# pcf1306p-SMD.net
KiCad netlist of a schematic drawn in EAGLE
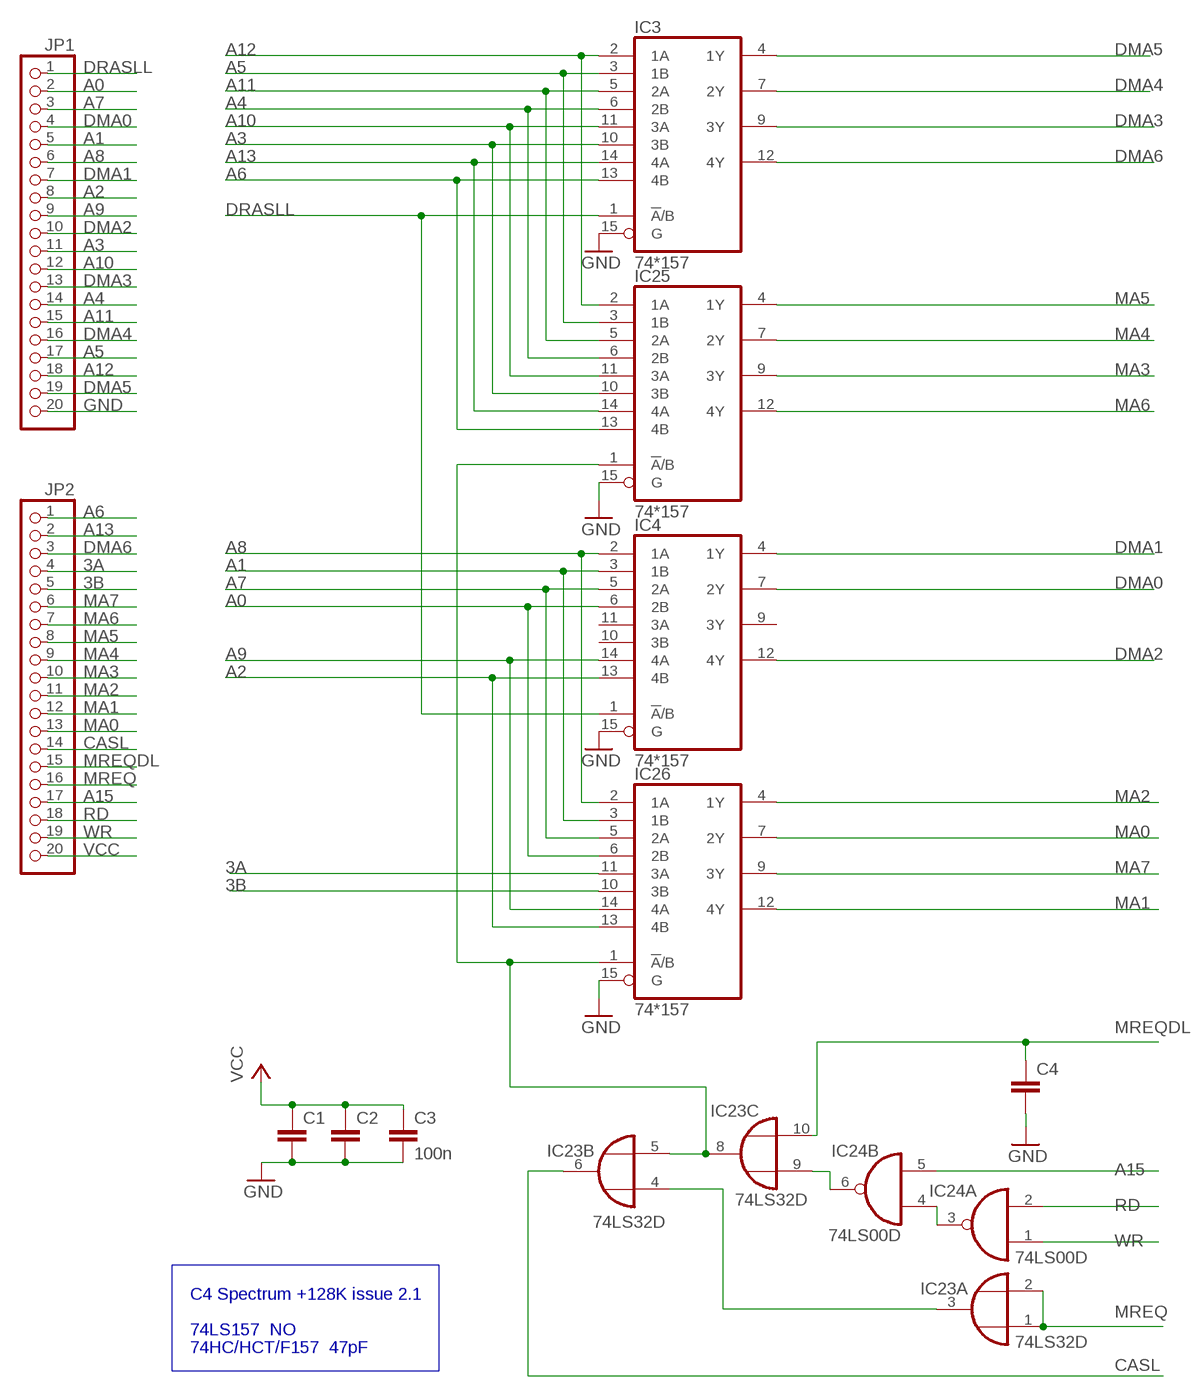
[diagram p0: schematic, sheet 1]

(export (version "E")
  (design (tool "Eeschema 10.0.6"))
  (components
    (comp (ref "C1")
      (value "C-EUC0603")
      (footprint "eagle-import:C0603")
      (libsource (lib "eagle-import") (part "C-EUC0603"))
    )
    (comp (ref "C2")
      (value "C-EUC0603")
      (footprint "eagle-import:C0603")
      (libsource (lib "eagle-import") (part "C-EUC0603"))
    )
    (comp (ref "C3")
      (value "100n")
      (footprint "eagle-import:C0603")
      (libsource (lib "eagle-import") (part "C-EUC0603"))
    )
    (comp (ref "C4")
      (value "C-EUC0805")
      (footprint "eagle-import:C0805")
      (libsource (lib "eagle-import") (part "C-EUC0805"))
    )
    (comp (ref "IC3")
      (value "74*157")
      (footprint "eagle-import:SO16")
      (libsource (lib "eagle-import") (part "74157DLS"))
    )
    (comp (ref "IC4")
      (value "74*157")
      (footprint "eagle-import:SO16")
      (libsource (lib "eagle-import") (part "74157DLS"))
    )
    (comp (ref "IC23")
      (value "74LS32D")
      (footprint "eagle-import:SO14")
      (libsource (lib "eagle-import") (part "7432DLS"))
    )
    (comp (ref "IC24")
      (value "74LS00D")
      (footprint "eagle-import:SO14")
      (libsource (lib "eagle-import") (part "7400DLS"))
    )
    (comp (ref "IC25")
      (value "74*157")
      (footprint "eagle-import:SO16")
      (libsource (lib "eagle-import") (part "74157DLS"))
    )
    (comp (ref "IC26")
      (value "74*157")
      (footprint "eagle-import:SO16")
      (libsource (lib "eagle-import") (part "74157DLS"))
    )
    (comp (ref "JP1")
      (value "PINHD-1X20")
      (footprint "eagle-import:1X20")
      (libsource (lib "eagle-import") (part "PINHD-1X20"))
    )
    (comp (ref "JP2")
      (value "PINHD-1X20")
      (footprint "eagle-import:1X20")
      (libsource (lib "eagle-import") (part "PINHD-1X20"))
    )
  )
  (nets
    (net (code "1") (name "/3A") (class "Default")
      (node (ref "IC26") (pin "11") (pinfunction "3A_11") (pintype "input"))
      (node (ref "JP2") (pin "4") (pinfunction "4_4") (pintype "passive"))
    )
    (net (code "2") (name "/3B") (class "Default")
      (node (ref "IC26") (pin "10") (pinfunction "3B_10") (pintype "input"))
      (node (ref "JP2") (pin "5") (pinfunction "5_5") (pintype "passive"))
    )
    (net (code "3") (name "/A0") (class "Default")
      (node (ref "IC26") (pin "6") (pinfunction "2B_6") (pintype "input"))
      (node (ref "IC4") (pin "6") (pinfunction "2B_6") (pintype "input"))
      (node (ref "JP1") (pin "2") (pinfunction "2_2") (pintype "passive"))
    )
    (net (code "4") (name "/A1") (class "Default")
      (node (ref "IC26") (pin "3") (pinfunction "1B_3") (pintype "input"))
      (node (ref "IC4") (pin "3") (pinfunction "1B_3") (pintype "input"))
      (node (ref "JP1") (pin "5") (pinfunction "5_5") (pintype "passive"))
    )
    (net (code "5") (name "/A2") (class "Default")
      (node (ref "IC26") (pin "13") (pinfunction "4B_13") (pintype "input"))
      (node (ref "IC4") (pin "13") (pinfunction "4B_13") (pintype "input"))
      (node (ref "JP1") (pin "8") (pinfunction "8_8") (pintype "passive"))
    )
    (net (code "6") (name "/A3") (class "Default")
      (node (ref "IC25") (pin "10") (pinfunction "3B_10") (pintype "input"))
      (node (ref "IC3") (pin "10") (pinfunction "3B_10") (pintype "input"))
      (node (ref "JP1") (pin "11") (pinfunction "11_11") (pintype "passive"))
    )
    (net (code "7") (name "/A4") (class "Default")
      (node (ref "IC25") (pin "6") (pinfunction "2B_6") (pintype "input"))
      (node (ref "IC3") (pin "6") (pinfunction "2B_6") (pintype "input"))
      (node (ref "JP1") (pin "14") (pinfunction "14_14") (pintype "passive"))
    )
    (net (code "8") (name "/A5") (class "Default")
      (node (ref "IC25") (pin "3") (pinfunction "1B_3") (pintype "input"))
      (node (ref "IC3") (pin "3") (pinfunction "1B_3") (pintype "input"))
      (node (ref "JP1") (pin "17") (pinfunction "17_17") (pintype "passive"))
    )
    (net (code "9") (name "/A6") (class "Default")
      (node (ref "IC25") (pin "13") (pinfunction "4B_13") (pintype "input"))
      (node (ref "IC3") (pin "13") (pinfunction "4B_13") (pintype "input"))
      (node (ref "JP2") (pin "1") (pinfunction "1_1") (pintype "passive"))
    )
    (net (code "10") (name "/A7") (class "Default")
      (node (ref "IC26") (pin "5") (pinfunction "2A_5") (pintype "input"))
      (node (ref "IC4") (pin "5") (pinfunction "2A_5") (pintype "input"))
      (node (ref "JP1") (pin "3") (pinfunction "3_3") (pintype "passive"))
    )
    (net (code "11") (name "/A8") (class "Default")
      (node (ref "IC26") (pin "2") (pinfunction "1A_2") (pintype "input"))
      (node (ref "IC4") (pin "2") (pinfunction "1A_2") (pintype "input"))
      (node (ref "JP1") (pin "6") (pinfunction "6_6") (pintype "passive"))
    )
    (net (code "12") (name "/A9") (class "Default")
      (node (ref "IC26") (pin "14") (pinfunction "4A_14") (pintype "input"))
      (node (ref "IC4") (pin "14") (pinfunction "4A_14") (pintype "input"))
      (node (ref "JP1") (pin "9") (pinfunction "9_9") (pintype "passive"))
    )
    (net (code "13") (name "/A10") (class "Default")
      (node (ref "IC25") (pin "11") (pinfunction "3A_11") (pintype "input"))
      (node (ref "IC3") (pin "11") (pinfunction "3A_11") (pintype "input"))
      (node (ref "JP1") (pin "12") (pinfunction "12_12") (pintype "passive"))
    )
    (net (code "14") (name "/A11") (class "Default")
      (node (ref "IC25") (pin "5") (pinfunction "2A_5") (pintype "input"))
      (node (ref "IC3") (pin "5") (pinfunction "2A_5") (pintype "input"))
      (node (ref "JP1") (pin "15") (pinfunction "15_15") (pintype "passive"))
    )
    (net (code "15") (name "/A12") (class "Default")
      (node (ref "IC25") (pin "2") (pinfunction "1A_2") (pintype "input"))
      (node (ref "IC3") (pin "2") (pinfunction "1A_2") (pintype "input"))
      (node (ref "JP1") (pin "18") (pinfunction "18_18") (pintype "passive"))
    )
    (net (code "16") (name "/A13") (class "Default")
      (node (ref "IC25") (pin "14") (pinfunction "4A_14") (pintype "input"))
      (node (ref "IC3") (pin "14") (pinfunction "4A_14") (pintype "input"))
      (node (ref "JP2") (pin "2") (pinfunction "2_2") (pintype "passive"))
    )
    (net (code "17") (name "/A15") (class "Default")
      (node (ref "IC24") (pin "5") (pinfunction "I1_5") (pintype "input"))
      (node (ref "JP2") (pin "17") (pinfunction "17_17") (pintype "passive"))
    )
    (net (code "18") (name "/CASL") (class "Default")
      (node (ref "IC23") (pin "6") (pinfunction "O_6") (pintype "output"))
      (node (ref "JP2") (pin "14") (pinfunction "14_14") (pintype "passive"))
    )
    (net (code "19") (name "/DMA0") (class "Default")
      (node (ref "IC4") (pin "7") (pinfunction "2Y_7") (pintype "output"))
      (node (ref "JP1") (pin "4") (pinfunction "4_4") (pintype "passive"))
    )
    (net (code "20") (name "/DMA1") (class "Default")
      (node (ref "IC4") (pin "4") (pinfunction "1Y_4") (pintype "output"))
      (node (ref "JP1") (pin "7") (pinfunction "7_7") (pintype "passive"))
    )
    (net (code "21") (name "/DMA2") (class "Default")
      (node (ref "IC4") (pin "12") (pinfunction "4Y_12") (pintype "output"))
      (node (ref "JP1") (pin "10") (pinfunction "10_10") (pintype "passive"))
    )
    (net (code "22") (name "/DMA3") (class "Default")
      (node (ref "IC3") (pin "9") (pinfunction "3Y_9") (pintype "output"))
      (node (ref "JP1") (pin "13") (pinfunction "13_13") (pintype "passive"))
    )
    (net (code "23") (name "/DMA4") (class "Default")
      (node (ref "IC3") (pin "7") (pinfunction "2Y_7") (pintype "output"))
      (node (ref "JP1") (pin "16") (pinfunction "16_16") (pintype "passive"))
    )
    (net (code "24") (name "/DMA5") (class "Default")
      (node (ref "IC3") (pin "4") (pinfunction "1Y_4") (pintype "output"))
      (node (ref "JP1") (pin "19") (pinfunction "19_19") (pintype "passive"))
    )
    (net (code "25") (name "/DMA6") (class "Default")
      (node (ref "IC3") (pin "12") (pinfunction "4Y_12") (pintype "output"))
      (node (ref "JP2") (pin "3") (pinfunction "3_3") (pintype "passive"))
    )
    (net (code "26") (name "/DRASLL") (class "Default")
      (node (ref "IC3") (pin "1") (pinfunction "~{A}/B_1") (pintype "input"))
      (node (ref "IC4") (pin "1") (pinfunction "~{A}/B_1") (pintype "input"))
      (node (ref "JP1") (pin "1") (pinfunction "1_1") (pintype "passive"))
    )
    (net (code "27") (name "/MA0") (class "Default")
      (node (ref "IC26") (pin "7") (pinfunction "2Y_7") (pintype "output"))
      (node (ref "JP2") (pin "13") (pinfunction "13_13") (pintype "passive"))
    )
    (net (code "28") (name "/MA1") (class "Default")
      (node (ref "IC26") (pin "12") (pinfunction "4Y_12") (pintype "output"))
      (node (ref "JP2") (pin "12") (pinfunction "12_12") (pintype "passive"))
    )
    (net (code "29") (name "/MA2") (class "Default")
      (node (ref "IC26") (pin "4") (pinfunction "1Y_4") (pintype "output"))
      (node (ref "JP2") (pin "11") (pinfunction "11_11") (pintype "passive"))
    )
    (net (code "30") (name "/MA3") (class "Default")
      (node (ref "IC25") (pin "9") (pinfunction "3Y_9") (pintype "output"))
      (node (ref "JP2") (pin "10") (pinfunction "10_10") (pintype "passive"))
    )
    (net (code "31") (name "/MA4") (class "Default")
      (node (ref "IC25") (pin "7") (pinfunction "2Y_7") (pintype "output"))
      (node (ref "JP2") (pin "9") (pinfunction "9_9") (pintype "passive"))
    )
    (net (code "32") (name "/MA5") (class "Default")
      (node (ref "IC25") (pin "4") (pinfunction "1Y_4") (pintype "output"))
      (node (ref "JP2") (pin "8") (pinfunction "8_8") (pintype "passive"))
    )
    (net (code "33") (name "/MA6") (class "Default")
      (node (ref "IC25") (pin "12") (pinfunction "4Y_12") (pintype "output"))
      (node (ref "JP2") (pin "7") (pinfunction "7_7") (pintype "passive"))
    )
    (net (code "34") (name "/MA7") (class "Default")
      (node (ref "IC26") (pin "9") (pinfunction "3Y_9") (pintype "output"))
      (node (ref "JP2") (pin "6") (pinfunction "6_6") (pintype "passive"))
    )
    (net (code "35") (name "/MREQ") (class "Default")
      (node (ref "IC23") (pin "1") (pinfunction "I0_1") (pintype "input"))
      (node (ref "IC23") (pin "2") (pinfunction "I1_2") (pintype "input"))
      (node (ref "JP2") (pin "16") (pinfunction "16_16") (pintype "passive"))
    )
    (net (code "36") (name "/MREQDL") (class "Default")
      (node (ref "C4") (pin "1") (pinfunction "1_1") (pintype "passive"))
      (node (ref "IC23") (pin "10") (pinfunction "I1_10") (pintype "input"))
      (node (ref "JP2") (pin "15") (pinfunction "15_15") (pintype "passive"))
    )
    (net (code "37") (name "/RD") (class "Default")
      (node (ref "IC24") (pin "2") (pinfunction "I1_2") (pintype "input"))
      (node (ref "JP2") (pin "18") (pinfunction "18_18") (pintype "passive"))
    )
    (net (code "38") (name "/WR") (class "Default")
      (node (ref "IC24") (pin "1") (pinfunction "I0_1") (pintype "input"))
      (node (ref "JP2") (pin "19") (pinfunction "19_19") (pintype "passive"))
    )
    (net (code "39") (name "GND") (class "Default")
      (node (ref "C1") (pin "2") (pinfunction "2_2") (pintype "passive"))
      (node (ref "C2") (pin "2") (pinfunction "2_2") (pintype "passive"))
      (node (ref "C3") (pin "2") (pinfunction "2_2") (pintype "passive"))
      (node (ref "C4") (pin "2") (pinfunction "2_2") (pintype "passive"))
      (node (ref "IC25") (pin "15") (pinfunction "G_15") (pintype "input"))
      (node (ref "IC26") (pin "15") (pinfunction "G_15") (pintype "input"))
      (node (ref "IC3") (pin "15") (pinfunction "G_15") (pintype "input"))
      (node (ref "IC4") (pin "15") (pinfunction "G_15") (pintype "input"))
      (node (ref "JP1") (pin "20") (pinfunction "20_20") (pintype "passive"))
    )
    (net (code "40") (name "Net-(IC23A-O)") (class "Default")
      (node (ref "IC23") (pin "3") (pinfunction "O_3") (pintype "output"))
      (node (ref "IC23") (pin "4") (pinfunction "I0_4") (pintype "input"))
    )
    (net (code "41") (name "Net-(IC23B-I1)") (class "Default")
      (node (ref "IC23") (pin "5") (pinfunction "I1_5") (pintype "input"))
      (node (ref "IC23") (pin "8") (pinfunction "O_8") (pintype "output"))
      (node (ref "IC25") (pin "1") (pinfunction "~{A}/B_1") (pintype "input"))
      (node (ref "IC26") (pin "1") (pinfunction "~{A}/B_1") (pintype "input"))
    )
    (net (code "42") (name "Net-(IC23C-I0)") (class "Default")
      (node (ref "IC23") (pin "9") (pinfunction "I0_9") (pintype "input"))
      (node (ref "IC24") (pin "6") (pinfunction "O_6") (pintype "output"))
    )
    (net (code "43") (name "Net-(IC24A-O)") (class "Default")
      (node (ref "IC24") (pin "3") (pinfunction "O_3") (pintype "output"))
      (node (ref "IC24") (pin "4") (pinfunction "I0_4") (pintype "input"))
    )
    (net (code "44") (name "VCC") (class "Default")
      (node (ref "C1") (pin "1") (pinfunction "1_1") (pintype "passive"))
      (node (ref "C2") (pin "1") (pinfunction "1_1") (pintype "passive"))
      (node (ref "C3") (pin "1") (pinfunction "1_1") (pintype "passive"))
      (node (ref "JP2") (pin "20") (pinfunction "20_20") (pintype "passive"))
    )
    (net (code "45") (name "unconnected-(IC4A-3A-Pad11)") (class "Default")
      (node (ref "IC4") (pin "11") (pinfunction "3A_11") (pintype "input"))
    )
    (net (code "46") (name "unconnected-(IC4A-3B-Pad10)") (class "Default")
      (node (ref "IC4") (pin "10") (pinfunction "3B_10") (pintype "input"))
    )
    (net (code "47") (name "unconnected-(IC4A-3Y-Pad9)") (class "Default")
      (node (ref "IC4") (pin "9") (pinfunction "3Y_9") (pintype "output"))
    )
  )
)
